# audio_sw.net
KiCad netlist of a schematic drawn in EAGLE
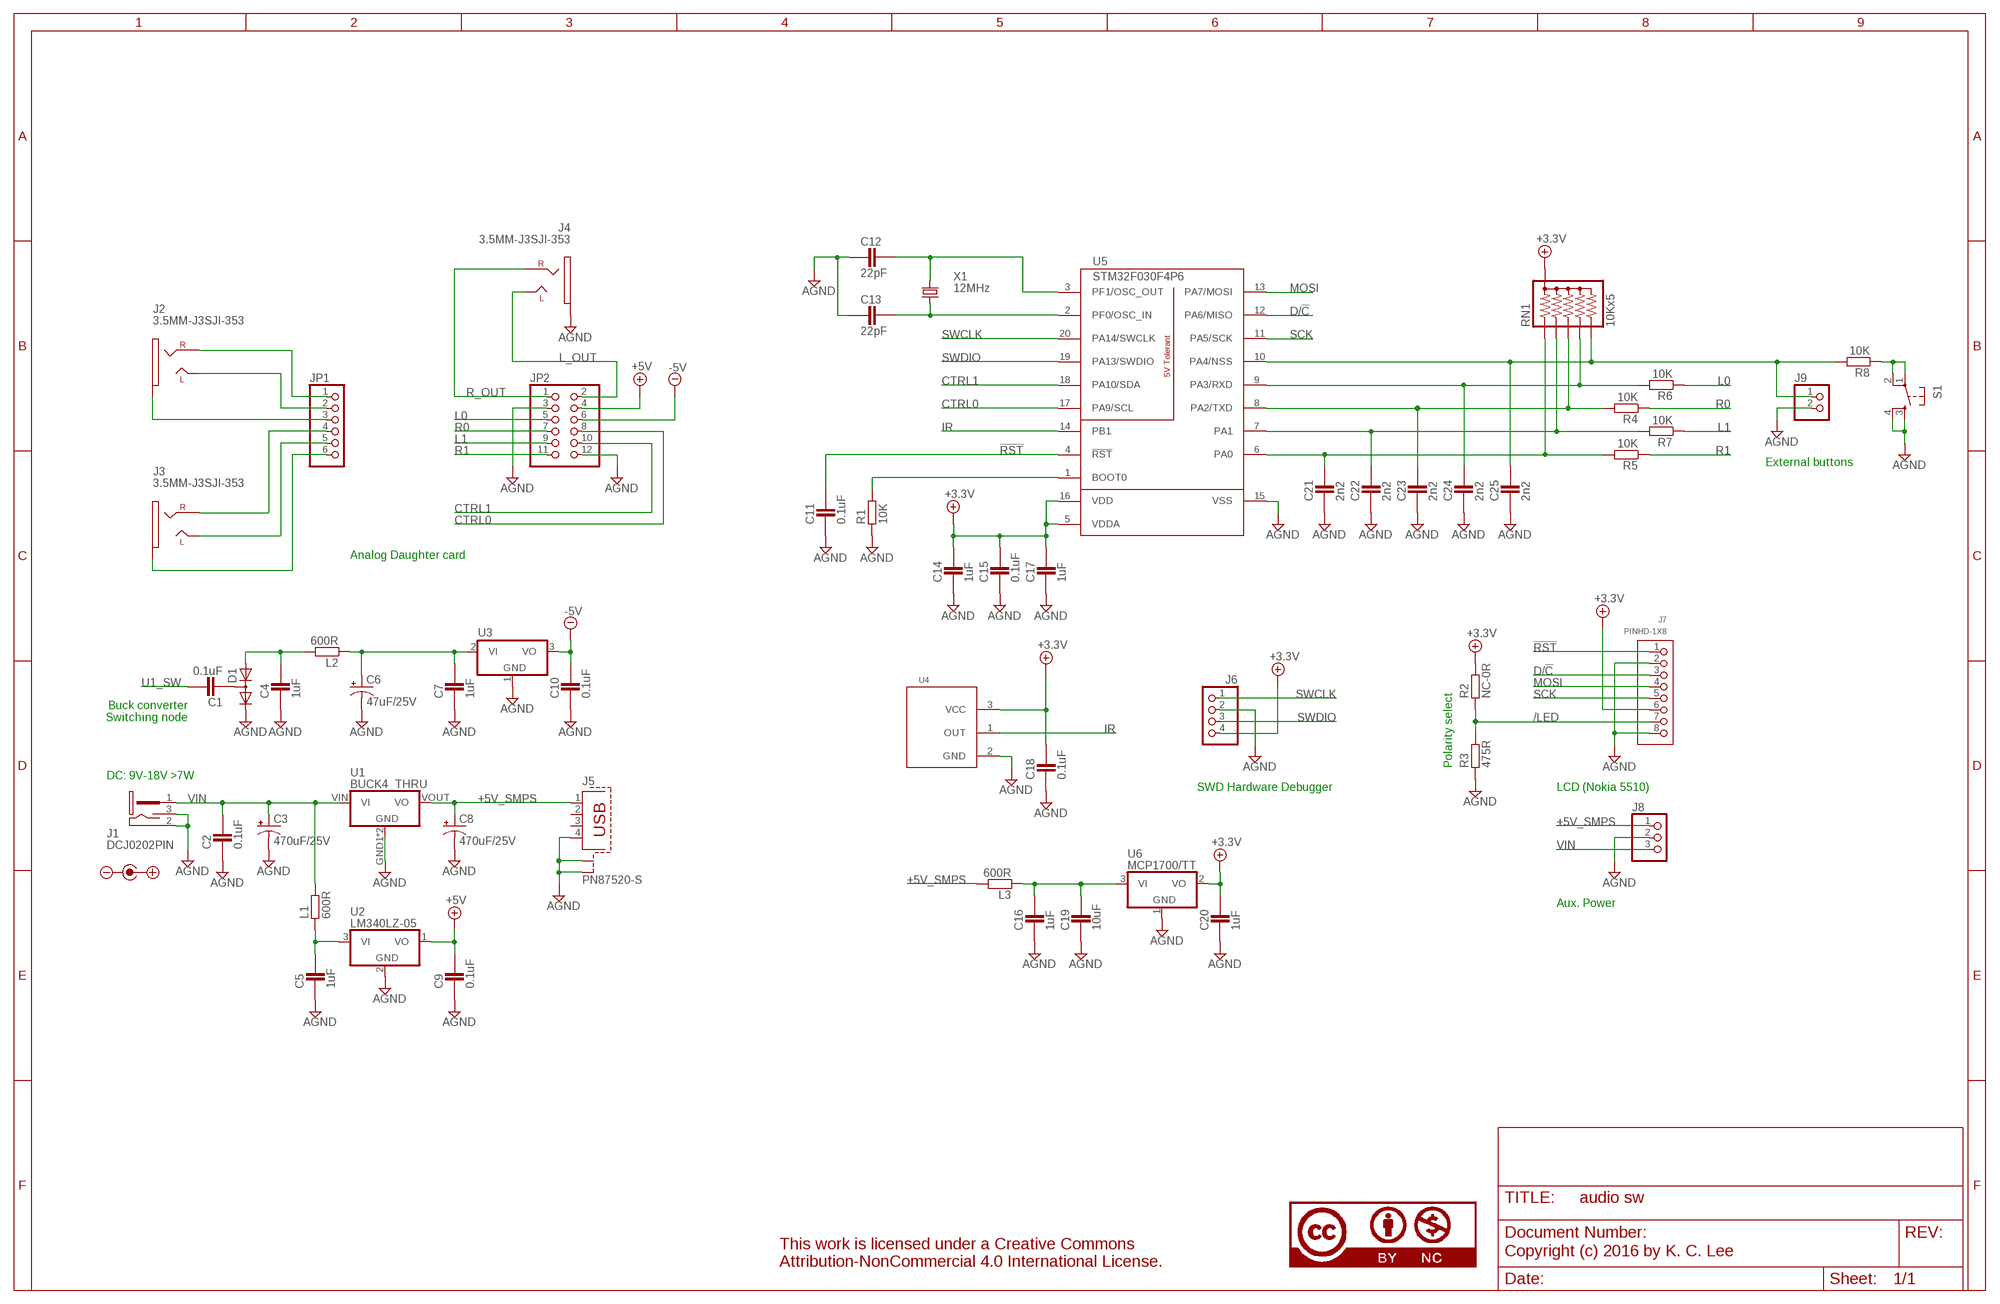
[diagram p0: schematic, sheet 1]

(export (version "E")
  (design (tool "Eeschema 10.0.6"))
  (components
    (comp (ref "$1_40_$")
      (value "CC-BY-NC100%")
      (footprint "eagle-import:CC-BY-NC-100")
      (libsource (lib "eagle-import") (part "CC-BY-NC100%"))
    )
    (comp (ref "C1")
      (value "0.1uF")
      (footprint "eagle-import:CAPC1608X92N")
      (libsource (lib "eagle-import") (part "CAPACITOR_0603"))
    )
    (comp (ref "C2")
      (value "0.1uF")
      (footprint "eagle-import:CAPC2012X145AN")
      (libsource (lib "eagle-import") (part "CAPACITOR_0805"))
    )
    (comp (ref "C3")
      (value "470uF/25V")
      (footprint "eagle-import:CPOL-RADIAL-470UF-25V")
      (libsource (lib "eagle-import") (part "CAP_POLPTH3"))
    )
    (comp (ref "C4")
      (value "1uF")
      (footprint "eagle-import:CAPC1608X92N")
      (libsource (lib "eagle-import") (part "CAPACITOR_0603"))
    )
    (comp (ref "C5")
      (value "1uF")
      (footprint "eagle-import:CAPC1608X92N")
      (libsource (lib "eagle-import") (part "CAPACITOR_0603"))
    )
    (comp (ref "C6")
      (value "47uF/25V")
      (footprint "eagle-import:CPOL-RADIAL-10UF-25V")
      (libsource (lib "eagle-import") (part "CAP_POLPTH2"))
    )
    (comp (ref "C7")
      (value "1uF")
      (footprint "eagle-import:CAPC1608X92N")
      (libsource (lib "eagle-import") (part "CAPACITOR_0603"))
    )
    (comp (ref "C8")
      (value "470uF/25V")
      (footprint "eagle-import:CPOL-RADIAL-470UF-25V")
      (libsource (lib "eagle-import") (part "CAP_POLPTH3"))
    )
    (comp (ref "C9")
      (value "0.1uF")
      (footprint "eagle-import:CAPC1608X92N")
      (libsource (lib "eagle-import") (part "CAPACITOR_0603"))
    )
    (comp (ref "C10")
      (value "0.1uF")
      (footprint "eagle-import:CAPC1608X92N")
      (libsource (lib "eagle-import") (part "CAPACITOR_0603"))
    )
    (comp (ref "C11")
      (value "0.1uF")
      (footprint "eagle-import:CAPC1608X92N")
      (libsource (lib "eagle-import") (part "CAPACITOR_0603"))
    )
    (comp (ref "C12")
      (value "22pF")
      (footprint "eagle-import:CAPC1608X92N")
      (libsource (lib "eagle-import") (part "CAPACITOR_0603"))
    )
    (comp (ref "C13")
      (value "22pF")
      (footprint "eagle-import:CAPC1608X92N")
      (libsource (lib "eagle-import") (part "CAPACITOR_0603"))
    )
    (comp (ref "C14")
      (value "1uF")
      (footprint "eagle-import:CAPC1608X92N")
      (libsource (lib "eagle-import") (part "CAPACITOR_0603"))
    )
    (comp (ref "C15")
      (value "0.1uF")
      (footprint "eagle-import:CAPC1608X92N")
      (libsource (lib "eagle-import") (part "CAPACITOR_0603"))
    )
    (comp (ref "C16")
      (value "1uF")
      (footprint "eagle-import:CAPC1608X92N")
      (libsource (lib "eagle-import") (part "CAPACITOR_0603"))
    )
    (comp (ref "C17")
      (value "1uF")
      (footprint "eagle-import:CAPC1608X92N")
      (libsource (lib "eagle-import") (part "CAPACITOR_0603"))
    )
    (comp (ref "C18")
      (value "0.1uF")
      (footprint "eagle-import:CAPC1608X92N")
      (libsource (lib "eagle-import") (part "CAPACITOR_0603"))
    )
    (comp (ref "C19")
      (value "10uF")
      (footprint "eagle-import:CAPC2012X145AN")
      (libsource (lib "eagle-import") (part "CAPACITOR_0805"))
    )
    (comp (ref "C20")
      (value "1uF")
      (footprint "eagle-import:CAPC1608X92N")
      (libsource (lib "eagle-import") (part "CAPACITOR_0603"))
    )
    (comp (ref "C21")
      (value "2n2")
      (footprint "eagle-import:CAPC1608X92N")
      (libsource (lib "eagle-import") (part "CAPACITOR_0603"))
    )
    (comp (ref "C22")
      (value "2n2")
      (footprint "eagle-import:CAPC1608X92N")
      (libsource (lib "eagle-import") (part "CAPACITOR_0603"))
    )
    (comp (ref "C23")
      (value "2n2")
      (footprint "eagle-import:CAPC1608X92N")
      (libsource (lib "eagle-import") (part "CAPACITOR_0603"))
    )
    (comp (ref "C24")
      (value "2n2")
      (footprint "eagle-import:CAPC1608X92N")
      (libsource (lib "eagle-import") (part "CAPACITOR_0603"))
    )
    (comp (ref "C25")
      (value "2n2")
      (footprint "eagle-import:CAPC1608X92N")
      (libsource (lib "eagle-import") (part "CAPACITOR_0603"))
    )
    (comp (ref "D1")
      (value "KA2KA_SOT-23")
      (footprint "eagle-import:SOT95P280X135-3N")
      (libsource (lib "eagle-import") (part "KA2KA_SOT-23"))
    )
    (comp (ref "J1")
      (value "DCJ0202PIN")
      (footprint "eagle-import:PJ-102A")
      (libsource (lib "eagle-import") (part "DCJ0202PIN"))
    )
    (comp (ref "J2")
      (value "3.5MM-J3SJI-353")
      (footprint "eagle-import:CUI-3MM")
      (libsource (lib "eagle-import") (part "3.5MM-J3SJI-353"))
    )
    (comp (ref "J3")
      (value "3.5MM-J3SJI-353")
      (footprint "eagle-import:CUI-3MM")
      (libsource (lib "eagle-import") (part "3.5MM-J3SJI-353"))
    )
    (comp (ref "J4")
      (value "3.5MM-J3SJI-353")
      (footprint "eagle-import:CUI-3MM")
      (libsource (lib "eagle-import") (part "3.5MM-J3SJI-353"))
    )
    (comp (ref "J5")
      (value "PN87520-S")
      (footprint "eagle-import:PN87520-S")
      (libsource (lib "eagle-import") (part "PN87520-S"))
    )
    (comp (ref "J6")
      (value "PINHD-1X4_2.54")
      (footprint "eagle-import:1X04")
      (libsource (lib "eagle-import") (part "PINHD-1X4_2.54"))
    )
    (comp (ref "J7")
      (value "PINHD-1X8")
      (footprint "eagle-import:1X08")
      (libsource (lib "eagle-import") (part "PINHD-1X8"))
    )
    (comp (ref "J8")
      (value "PINHD-1X3")
      (footprint "eagle-import:1X03")
      (libsource (lib "eagle-import") (part "PINHD-1X3"))
    )
    (comp (ref "J9")
      (value "PINHD-1X2_2.54")
      (footprint "eagle-import:1X02")
      (libsource (lib "eagle-import") (part "PINHD-1X2_2.54"))
    )
    (comp (ref "JP1")
      (value "PINHD-1X6")
      (footprint "eagle-import:1X06")
      (libsource (lib "eagle-import") (part "PINHD-1X6"))
    )
    (comp (ref "JP2")
      (value "PINHD-2X6_2.54")
      (footprint "eagle-import:2X06")
      (libsource (lib "eagle-import") (part "PINHD-2X6_2.54"))
    )
    (comp (ref "L1")
      (value "600R")
      (footprint "eagle-import:RESC2012X70N")
      (libsource (lib "eagle-import") (part "RESISTOR_0805"))
    )
    (comp (ref "L2")
      (value "600R")
      (footprint "eagle-import:RESC2012X70N")
      (libsource (lib "eagle-import") (part "RESISTOR_0805"))
    )
    (comp (ref "L3")
      (value "600R")
      (footprint "eagle-import:RESC2012X70N")
      (libsource (lib "eagle-import") (part "RESISTOR_0805"))
    )
    (comp (ref "R1")
      (value "10K")
      (footprint "eagle-import:RESC1608X55N")
      (libsource (lib "eagle-import") (part "RESISTOR_0603"))
    )
    (comp (ref "R2")
      (value "NC-0R")
      (footprint "eagle-import:RESC1608X55N")
      (libsource (lib "eagle-import") (part "RESISTOR_0603"))
    )
    (comp (ref "R3")
      (value "475R")
      (footprint "eagle-import:RESC1608X55N")
      (libsource (lib "eagle-import") (part "RESISTOR_0603"))
    )
    (comp (ref "R4")
      (value "10K")
      (footprint "eagle-import:RESC1608X55N")
      (libsource (lib "eagle-import") (part "RESISTOR_0603"))
    )
    (comp (ref "R5")
      (value "10K")
      (footprint "eagle-import:RESC1608X55N")
      (libsource (lib "eagle-import") (part "RESISTOR_0603"))
    )
    (comp (ref "R6")
      (value "10K")
      (footprint "eagle-import:RESC1608X55N")
      (libsource (lib "eagle-import") (part "RESISTOR_0603"))
    )
    (comp (ref "R7")
      (value "10K")
      (footprint "eagle-import:RESC1608X55N")
      (libsource (lib "eagle-import") (part "RESISTOR_0603"))
    )
    (comp (ref "R8")
      (value "10K")
      (footprint "eagle-import:RESC1608X55N")
      (libsource (lib "eagle-import") (part "RESISTOR_0603"))
    )
    (comp (ref "RN1")
      (value "10Kx5")
      (footprint "eagle-import:RPACK-SIP-PTH-5")
      (libsource (lib "eagle-import") (part "RPACK-BUSSED-SIP-PTH-5"))
    )
    (comp (ref "S1")
      (value "TAC_SWITCHPTH")
      (footprint "eagle-import:TACTILE-PTH")
      (libsource (lib "eagle-import") (part "TAC_SWITCHPTH"))
    )
    (comp (ref "U$1")
      (value "POLARITY")
      (footprint "eagle-import:POLARITY")
      (libsource (lib "eagle-import") (part "POLARITY"))
    )
    (comp (ref "U1")
      (value "BUCK4_THRU")
      (footprint "eagle-import:PWR4_THRU")
      (libsource (lib "eagle-import") (part "BUCK4_THRU"))
    )
    (comp (ref "U2")
      (value "LM340LZ-05")
      (footprint "eagle-import:TO92-CLP")
      (libsource (lib "eagle-import") (part "LM340?-LZ05"))
    )
    (comp (ref "U3")
      (value "79L05Z")
      (footprint "eagle-import:TO92-CLP")
      (libsource (lib "eagle-import") (part "79ZL05"))
    )
    (comp (ref "U4")
      (value "AX-1838HS")
      (footprint "eagle-import:AX1838")
      (libsource (lib "eagle-import") (part "AX-1838HS"))
    )
    (comp (ref "U5")
      (value "STM32F030F4P6")
      (footprint "eagle-import:TSSOP20")
      (libsource (lib "eagle-import") (part "STM32F030F4P6"))
    )
    (comp (ref "U6")
      (value "MCP1700/TT")
      (footprint "eagle-import:SOT95P280X135-3N")
      (libsource (lib "eagle-import") (part "MCP1700/TT"))
    )
    (comp (ref "X1")
      (value "12MHz")
      (footprint "eagle-import:HC49U-V")
      (libsource (lib "eagle-import") (part "CRYSTALHC49U-V"))
    )
  )
  (nets
    (net (code "1") (name "+3.3V") (class "Default")
      (node (ref "C14") (pin "2") (pinfunction "2_2") (pintype "passive"))
      (node (ref "C15") (pin "2") (pinfunction "2_2") (pintype "passive"))
      (node (ref "C17") (pin "2") (pinfunction "2_2") (pintype "passive"))
      (node (ref "C18") (pin "2") (pinfunction "2_2") (pintype "passive"))
      (node (ref "C20") (pin "2") (pinfunction "2_2") (pintype "passive"))
      (node (ref "J6") (pin "4") (pinfunction "4_4") (pintype "passive"))
      (node (ref "J7") (pin "6") (pinfunction "P$6_6") (pintype "bidirectional"))
      (node (ref "R2") (pin "2") (pinfunction "2_2") (pintype "passive"))
      (node (ref "RN1") (pin "P$1") (pinfunction "1_P$1") (pintype "passive"))
      (node (ref "U4") (pin "3") (pinfunction "VCC_3") (pintype "bidirectional"))
      (node (ref "U5") (pin "16") (pinfunction "VDD_16") (pintype "input"))
      (node (ref "U5") (pin "5") (pinfunction "VDDA_5") (pintype "input"))
      (node (ref "U6") (pin "2") (pinfunction "VO_2") (pintype "passive"))
    )
    (net (code "2") (name "+5V") (class "Default")
      (node (ref "C9") (pin "2") (pinfunction "2_2") (pintype "passive"))
      (node (ref "JP2") (pin "4") (pinfunction "4_4") (pintype "passive"))
      (node (ref "U2") (pin "1") (pinfunction "VO_1") (pintype "passive"))
    )
    (net (code "3") (name "-5V") (class "Default")
      (node (ref "C10") (pin "2") (pinfunction "2_2") (pintype "passive"))
      (node (ref "JP2") (pin "6") (pinfunction "6_6") (pintype "passive"))
      (node (ref "U3") (pin "3") (pinfunction "VO_3") (pintype "passive"))
    )
    (net (code "4") (name "/+5V_SMPS") (class "Default")
      (node (ref "C8") (pin "+") (pinfunction "+_+") (pintype "passive"))
      (node (ref "J5") (pin "1") (pinfunction "1_1") (pintype "passive"))
      (node (ref "J8") (pin "1") (pinfunction "1_1") (pintype "passive"))
      (node (ref "L3") (pin "2") (pinfunction "2_2") (pintype "passive"))
      (node (ref "U1") (pin "VOUT") (pinfunction "VO_VOUT") (pintype "passive"))
    )
    (net (code "5") (name "/CTRL0") (class "Default")
      (node (ref "JP2") (pin "8") (pinfunction "8_8") (pintype "passive"))
      (node (ref "U5") (pin "17") (pinfunction "PA9/SCL_17") (pintype "bidirectional"))
    )
    (net (code "6") (name "/CTRL1") (class "Default")
      (node (ref "JP2") (pin "10") (pinfunction "10_10") (pintype "passive"))
      (node (ref "U5") (pin "18") (pinfunction "PA10/SDA_18") (pintype "bidirectional"))
    )
    (net (code "7") (name "/D{slash}~{C}") (class "Default")
      (node (ref "J7") (pin "3") (pinfunction "P$3_3") (pintype "bidirectional"))
      (node (ref "U5") (pin "12") (pinfunction "PA6/MISO_12") (pintype "bidirectional"))
    )
    (net (code "8") (name "/IR") (class "Default")
      (node (ref "U4") (pin "1") (pinfunction "OUT_1") (pintype "bidirectional"))
      (node (ref "U5") (pin "14") (pinfunction "PB1_14") (pintype "bidirectional"))
    )
    (net (code "9") (name "/L0") (class "Default")
      (node (ref "JP2") (pin "5") (pinfunction "5_5") (pintype "passive"))
      (node (ref "R6") (pin "1") (pinfunction "1_1") (pintype "passive"))
    )
    (net (code "10") (name "/L1") (class "Default")
      (node (ref "JP2") (pin "9") (pinfunction "9_9") (pintype "passive"))
      (node (ref "R7") (pin "1") (pinfunction "1_1") (pintype "passive"))
    )
    (net (code "11") (name "/L_OUT") (class "Default")
      (node (ref "J4") (pin "2") (pinfunction "5_2") (pintype "bidirectional"))
      (node (ref "JP2") (pin "2") (pinfunction "2_2") (pintype "passive"))
    )
    (net (code "12") (name "/MOSI") (class "Default")
      (node (ref "J7") (pin "4") (pinfunction "P$4_4") (pintype "bidirectional"))
      (node (ref "U5") (pin "13") (pinfunction "PA7/MOSI_13") (pintype "bidirectional"))
    )
    (net (code "13") (name "/R0") (class "Default")
      (node (ref "JP2") (pin "7") (pinfunction "7_7") (pintype "passive"))
      (node (ref "R4") (pin "1") (pinfunction "1_1") (pintype "passive"))
    )
    (net (code "14") (name "/R1") (class "Default")
      (node (ref "JP2") (pin "11") (pinfunction "11_11") (pintype "passive"))
      (node (ref "R5") (pin "1") (pinfunction "1_1") (pintype "passive"))
    )
    (net (code "15") (name "/R_OUT") (class "Default")
      (node (ref "J4") (pin "3") (pinfunction "2_3") (pintype "bidirectional"))
      (node (ref "JP2") (pin "1") (pinfunction "1_1") (pintype "passive"))
    )
    (net (code "16") (name "/SCK") (class "Default")
      (node (ref "J7") (pin "5") (pinfunction "P$5_5") (pintype "bidirectional"))
      (node (ref "U5") (pin "11") (pinfunction "PA5/SCK_11") (pintype "bidirectional"))
    )
    (net (code "17") (name "/SWCLK") (class "Default")
      (node (ref "J6") (pin "1") (pinfunction "1_1") (pintype "passive"))
      (node (ref "U5") (pin "20") (pinfunction "PA14/SWCLK_20") (pintype "bidirectional"))
    )
    (net (code "18") (name "/SWDIO") (class "Default")
      (node (ref "J6") (pin "3") (pinfunction "3_3") (pintype "passive"))
      (node (ref "U5") (pin "19") (pinfunction "PA13/SWDIO_19") (pintype "bidirectional"))
    )
    (net (code "19") (name "/U1_SW") (class "Default")
      (node (ref "C1") (pin "2") (pinfunction "2_2") (pintype "passive"))
    )
    (net (code "20") (name "/VIN") (class "Default")
      (node (ref "C2") (pin "2") (pinfunction "2_2") (pintype "passive"))
      (node (ref "C3") (pin "+") (pinfunction "+_+") (pintype "passive"))
      (node (ref "J1") (pin "1") (pinfunction "1_1") (pintype "passive"))
      (node (ref "J8") (pin "3") (pinfunction "3_3") (pintype "passive"))
      (node (ref "L1") (pin "2") (pinfunction "2_2") (pintype "passive"))
      (node (ref "U1") (pin "VIN") (pinfunction "VI_VIN") (pintype "input"))
    )
    (net (code "21") (name "/{slash}LED") (class "Default")
      (node (ref "J7") (pin "7") (pinfunction "P$7_7") (pintype "bidirectional"))
      (node (ref "R2") (pin "1") (pinfunction "1_1") (pintype "passive"))
      (node (ref "R3") (pin "2") (pinfunction "2_2") (pintype "passive"))
    )
    (net (code "22") (name "/~{RST}") (class "Default")
      (node (ref "C11") (pin "2") (pinfunction "2_2") (pintype "passive"))
      (node (ref "J7") (pin "1") (pinfunction "P$1_1") (pintype "bidirectional"))
      (node (ref "U5") (pin "4") (pinfunction "~{RST}_4") (pintype "input"))
    )
    (net (code "23") (name "AGND") (class "Default")
      (node (ref "C10") (pin "1") (pinfunction "1_1") (pintype "passive"))
      (node (ref "C11") (pin "1") (pinfunction "1_1") (pintype "passive"))
      (node (ref "C12") (pin "1") (pinfunction "1_1") (pintype "passive"))
      (node (ref "C13") (pin "1") (pinfunction "1_1") (pintype "passive"))
      (node (ref "C14") (pin "1") (pinfunction "1_1") (pintype "passive"))
      (node (ref "C15") (pin "1") (pinfunction "1_1") (pintype "passive"))
      (node (ref "C16") (pin "1") (pinfunction "1_1") (pintype "passive"))
      (node (ref "C17") (pin "1") (pinfunction "1_1") (pintype "passive"))
      (node (ref "C18") (pin "1") (pinfunction "1_1") (pintype "passive"))
      (node (ref "C19") (pin "1") (pinfunction "1_1") (pintype "passive"))
      (node (ref "C2") (pin "1") (pinfunction "1_1") (pintype "passive"))
      (node (ref "C20") (pin "1") (pinfunction "1_1") (pintype "passive"))
      (node (ref "C21") (pin "1") (pinfunction "1_1") (pintype "passive"))
      (node (ref "C22") (pin "1") (pinfunction "1_1") (pintype "passive"))
      (node (ref "C23") (pin "1") (pinfunction "1_1") (pintype "passive"))
      (node (ref "C24") (pin "1") (pinfunction "1_1") (pintype "passive"))
      (node (ref "C25") (pin "1") (pinfunction "1_1") (pintype "passive"))
      (node (ref "C3") (pin "-") (pinfunction "-_-") (pintype "passive"))
      (node (ref "C4") (pin "1") (pinfunction "1_1") (pintype "passive"))
      (node (ref "C5") (pin "1") (pinfunction "1_1") (pintype "passive"))
      (node (ref "C6") (pin "2") (pinfunction "-_2") (pintype "passive"))
      (node (ref "C7") (pin "1") (pinfunction "1_1") (pintype "passive"))
      (node (ref "C8") (pin "-") (pinfunction "-_-") (pintype "passive"))
      (node (ref "C9") (pin "1") (pinfunction "1_1") (pintype "passive"))
      (node (ref "D1") (pin "2") (pinfunction "K_2") (pintype "passive"))
      (node (ref "J1") (pin "2") (pinfunction "3_2") (pintype "passive"))
      (node (ref "J1") (pin "3") (pinfunction "2_3") (pintype "passive"))
      (node (ref "J4") (pin "1") (pinfunction "1_1") (pintype "bidirectional"))
      (node (ref "J5") (pin "4") (pinfunction "4_4") (pintype "passive"))
      (node (ref "J5") (pin "S1") (pinfunction "S1_S1") (pintype "passive"))
      (node (ref "J5") (pin "S2") (pinfunction "S2_S2") (pintype "passive"))
      (node (ref "J6") (pin "2") (pinfunction "2_2") (pintype "passive"))
      (node (ref "J7") (pin "2") (pinfunction "P$2_2") (pintype "bidirectional"))
      (node (ref "J7") (pin "8") (pinfunction "P$8_8") (pintype "bidirectional"))
      (node (ref "J8") (pin "2") (pinfunction "2_2") (pintype "passive"))
      (node (ref "J9") (pin "2") (pinfunction "2_2") (pintype "passive"))
      (node (ref "JP2") (pin "12") (pinfunction "12_12") (pintype "passive"))
      (node (ref "JP2") (pin "3") (pinfunction "3_3") (pintype "passive"))
      (node (ref "R1") (pin "1") (pinfunction "1_1") (pintype "passive"))
      (node (ref "R3") (pin "1") (pinfunction "1_1") (pintype "passive"))
      (node (ref "S1") (pin "3") (pinfunction "3_3") (pintype "passive"))
      (node (ref "S1") (pin "4") (pinfunction "4_4") (pintype "passive"))
      (node (ref "U1") (pin "GND1") (pinfunction "GND_GND1") (pintype "passive"))
      (node (ref "U1") (pin "GND2") (pinfunction "GND_GND2") (pintype "passive"))
      (node (ref "U2") (pin "2") (pinfunction "GND_2") (pintype "passive"))
      (node (ref "U3") (pin "1") (pinfunction "GND_1") (pintype "passive"))
      (node (ref "U4") (pin "2") (pinfunction "GND_2") (pintype "bidirectional"))
      (node (ref "U5") (pin "15") (pinfunction "VSS_15") (pintype "input"))
      (node (ref "U6") (pin "1") (pinfunction "GND_1") (pintype "passive"))
    )
    (net (code "24") (name "Net-(C6-+)") (class "Default")
      (node (ref "C6") (pin "1") (pinfunction "+_1") (pintype "passive"))
      (node (ref "C7") (pin "2") (pinfunction "2_2") (pintype "passive"))
      (node (ref "L2") (pin "1") (pinfunction "1_1") (pintype "passive"))
      (node (ref "U3") (pin "2") (pinfunction "VI_2") (pintype "input"))
    )
    (net (code "25") (name "Net-(D1-A)") (class "Default")
      (node (ref "C4") (pin "2") (pinfunction "2_2") (pintype "passive"))
      (node (ref "D1") (pin "1") (pinfunction "A_1") (pintype "passive"))
      (node (ref "L2") (pin "2") (pinfunction "2_2") (pintype "passive"))
    )
    (net (code "26") (name "Net-(D1-KA)") (class "Default")
      (node (ref "C1") (pin "1") (pinfunction "1_1") (pintype "passive"))
      (node (ref "D1") (pin "3") (pinfunction "KA_3") (pintype "passive"))
    )
    (net (code "27") (name "Net-(J2-2)") (class "Default")
      (node (ref "J2") (pin "3") (pinfunction "2_3") (pintype "bidirectional"))
      (node (ref "JP1") (pin "1") (pinfunction "1_1") (pintype "passive"))
    )
    (net (code "28") (name "Net-(J2-5)") (class "Default")
      (node (ref "J2") (pin "2") (pinfunction "5_2") (pintype "bidirectional"))
      (node (ref "JP1") (pin "2") (pinfunction "2_2") (pintype "passive"))
    )
    (net (code "29") (name "Net-(J2-Pad1)") (class "Default")
      (node (ref "J2") (pin "1") (pinfunction "1_1") (pintype "bidirectional"))
      (node (ref "JP1") (pin "3") (pinfunction "3_3") (pintype "passive"))
    )
    (net (code "30") (name "Net-(J3-2)") (class "Default")
      (node (ref "J3") (pin "3") (pinfunction "2_3") (pintype "bidirectional"))
      (node (ref "JP1") (pin "4") (pinfunction "4_4") (pintype "passive"))
    )
    (net (code "31") (name "Net-(J3-5)") (class "Default")
      (node (ref "J3") (pin "2") (pinfunction "5_2") (pintype "bidirectional"))
      (node (ref "JP1") (pin "5") (pinfunction "5_5") (pintype "passive"))
    )
    (net (code "32") (name "Net-(J3-Pad1)") (class "Default")
      (node (ref "J3") (pin "1") (pinfunction "1_1") (pintype "bidirectional"))
      (node (ref "JP1") (pin "6") (pinfunction "6_6") (pintype "passive"))
    )
    (net (code "33") (name "Net-(R8-Pad1)") (class "Default")
      (node (ref "R8") (pin "1") (pinfunction "1_1") (pintype "passive"))
      (node (ref "S1") (pin "1") (pinfunction "1_1") (pintype "passive"))
      (node (ref "S1") (pin "2") (pinfunction "2_2") (pintype "passive"))
    )
    (net (code "34") (name "Net-(RN1-2)") (class "Default")
      (node (ref "C21") (pin "2") (pinfunction "2_2") (pintype "passive"))
      (node (ref "R5") (pin "2") (pinfunction "2_2") (pintype "passive"))
      (node (ref "RN1") (pin "P$2") (pinfunction "2_P$2") (pintype "passive"))
      (node (ref "U5") (pin "6") (pinfunction "PA0_6") (pintype "bidirectional"))
    )
    (net (code "35") (name "Net-(RN1-3)") (class "Default")
      (node (ref "C22") (pin "2") (pinfunction "2_2") (pintype "passive"))
      (node (ref "R7") (pin "2") (pinfunction "2_2") (pintype "passive"))
      (node (ref "RN1") (pin "P$3") (pinfunction "3_P$3") (pintype "passive"))
      (node (ref "U5") (pin "7") (pinfunction "PA1_7") (pintype "bidirectional"))
    )
    (net (code "36") (name "Net-(RN1-4)") (class "Default")
      (node (ref "C23") (pin "2") (pinfunction "2_2") (pintype "passive"))
      (node (ref "R4") (pin "2") (pinfunction "2_2") (pintype "passive"))
      (node (ref "RN1") (pin "P$4") (pinfunction "4_P$4") (pintype "passive"))
      (node (ref "U5") (pin "8") (pinfunction "PA2/TXD_8") (pintype "bidirectional"))
    )
    (net (code "37") (name "Net-(RN1-5)") (class "Default")
      (node (ref "C24") (pin "2") (pinfunction "2_2") (pintype "passive"))
      (node (ref "R6") (pin "2") (pinfunction "2_2") (pintype "passive"))
      (node (ref "RN1") (pin "P$5") (pinfunction "5_P$5") (pintype "passive"))
      (node (ref "U5") (pin "9") (pinfunction "PA3/RXD_9") (pintype "bidirectional"))
    )
    (net (code "38") (name "Net-(RN1-6)") (class "Default")
      (node (ref "C25") (pin "2") (pinfunction "2_2") (pintype "passive"))
      (node (ref "J9") (pin "1") (pinfunction "1_1") (pintype "passive"))
      (node (ref "R8") (pin "2") (pinfunction "2_2") (pintype "passive"))
      (node (ref "RN1") (pin "P$6") (pinfunction "6_P$6") (pintype "passive"))
      (node (ref "U5") (pin "10") (pinfunction "PA4/NSS_10") (pintype "bidirectional"))
    )
    (net (code "39") (name "Net-(U2-VI)") (class "Default")
      (node (ref "C5") (pin "2") (pinfunction "2_2") (pintype "passive"))
      (node (ref "L1") (pin "1") (pinfunction "1_1") (pintype "passive"))
      (node (ref "U2") (pin "3") (pinfunction "VI_3") (pintype "input"))
    )
    (net (code "40") (name "Net-(U5-BOOT0)") (class "Default")
      (node (ref "R1") (pin "2") (pinfunction "2_2") (pintype "passive"))
      (node (ref "U5") (pin "1") (pinfunction "BOOT0_1") (pintype "input"))
    )
    (net (code "41") (name "Net-(U5-PF0{slash}OSC_IN)") (class "Default")
      (node (ref "C13") (pin "2") (pinfunction "2_2") (pintype "passive"))
      (node (ref "U5") (pin "2") (pinfunction "PF0/OSC_IN_2") (pintype "input"))
      (node (ref "X1") (pin "1") (pinfunction "1_1") (pintype "passive"))
    )
    (net (code "42") (name "Net-(U5-PF1{slash}OSC_OUT)") (class "Default")
      (node (ref "C12") (pin "2") (pinfunction "2_2") (pintype "passive"))
      (node (ref "U5") (pin "3") (pinfunction "PF1/OSC_OUT_3") (pintype "output"))
      (node (ref "X1") (pin "2") (pinfunction "2_2") (pintype "passive"))
    )
    (net (code "43") (name "Net-(U6-VI)") (class "Default")
      (node (ref "C16") (pin "2") (pinfunction "2_2") (pintype "passive"))
      (node (ref "C19") (pin "2") (pinfunction "2_2") (pintype "passive"))
      (node (ref "L3") (pin "1") (pinfunction "1_1") (pintype "passive"))
      (node (ref "U6") (pin "3") (pinfunction "VI_3") (pintype "input"))
    )
    (net (code "44") (name "unconnected-(J5-Pad2)") (class "Default")
      (node (ref "J5") (pin "2") (pinfunction "2_2") (pintype "passive"))
    )
    (net (code "45") (name "unconnected-(J5-Pad3)") (class "Default")
      (node (ref "J5") (pin "3") (pinfunction "3_3") (pintype "passive"))
    )
  )
)
